# MAX11609EEE-Breakout-Board.net
KiCad netlist of a schematic drawn in EAGLE
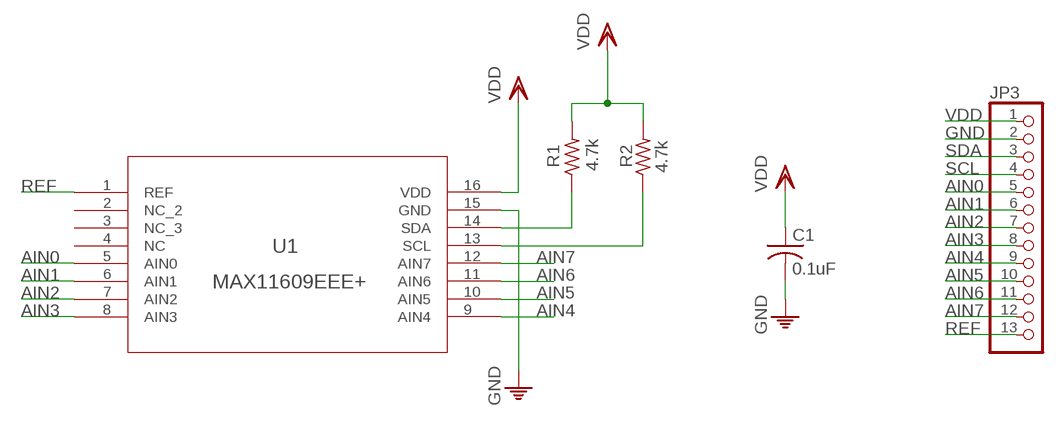
[diagram p0: schematic, sheet 1]

(export (version "E")
  (design (tool "Eeschema 10.0.6"))
  (components
    (comp (ref "C1")
      (value "0.1uF")
      (footprint "eagle-import:C0805")
      (libsource (lib "eagle-import") (part "C-USC0805"))
    )
    (comp (ref "JP3")
      (value "PINHD-1X13")
      (footprint "eagle-import:1X13")
      (libsource (lib "eagle-import") (part "PINHD-1X13"))
    )
    (comp (ref "R1")
      (value "4.7k")
      (footprint "eagle-import:R0805")
      (libsource (lib "eagle-import") (part "R-US_R0805"))
    )
    (comp (ref "R2")
      (value "4.7k")
      (footprint "eagle-import:R0805")
      (libsource (lib "eagle-import") (part "R-US_R0805"))
    )
    (comp (ref "U1")
      (value "MAX11609EEE+")
      (footprint "eagle-import:21-0055H_16")
      (libsource (lib "eagle-import") (part "MAX11609EEE+"))
    )
  )
  (nets
    (net (code "1") (name "/AIN0") (class "Default")
      (node (ref "JP3") (pin "5") (pinfunction "5_5") (pintype "passive"))
      (node (ref "U1") (pin "5") (pinfunction "AIN0_5") (pintype "input"))
    )
    (net (code "2") (name "/AIN1") (class "Default")
      (node (ref "JP3") (pin "6") (pinfunction "6_6") (pintype "passive"))
      (node (ref "U1") (pin "6") (pinfunction "AIN1_6") (pintype "input"))
    )
    (net (code "3") (name "/AIN2") (class "Default")
      (node (ref "JP3") (pin "7") (pinfunction "7_7") (pintype "passive"))
      (node (ref "U1") (pin "7") (pinfunction "AIN2_7") (pintype "input"))
    )
    (net (code "4") (name "/AIN3") (class "Default")
      (node (ref "JP3") (pin "8") (pinfunction "8_8") (pintype "passive"))
      (node (ref "U1") (pin "8") (pinfunction "AIN3_8") (pintype "input"))
    )
    (net (code "5") (name "/AIN4") (class "Default")
      (node (ref "JP3") (pin "9") (pinfunction "9_9") (pintype "passive"))
      (node (ref "U1") (pin "9") (pinfunction "AIN4_9") (pintype "input"))
    )
    (net (code "6") (name "/AIN5") (class "Default")
      (node (ref "JP3") (pin "10") (pinfunction "10_10") (pintype "passive"))
      (node (ref "U1") (pin "10") (pinfunction "AIN5_10") (pintype "input"))
    )
    (net (code "7") (name "/AIN6") (class "Default")
      (node (ref "JP3") (pin "11") (pinfunction "11_11") (pintype "passive"))
      (node (ref "U1") (pin "11") (pinfunction "AIN6_11") (pintype "input"))
    )
    (net (code "8") (name "/AIN7") (class "Default")
      (node (ref "JP3") (pin "12") (pinfunction "12_12") (pintype "passive"))
      (node (ref "U1") (pin "12") (pinfunction "AIN7_12") (pintype "input"))
    )
    (net (code "9") (name "/REF") (class "Default")
      (node (ref "JP3") (pin "13") (pinfunction "13_13") (pintype "passive"))
      (node (ref "U1") (pin "1") (pinfunction "REF_1") (pintype "passive"))
    )
    (net (code "10") (name "/SCL") (class "Default")
      (node (ref "JP3") (pin "4") (pinfunction "4_4") (pintype "passive"))
      (node (ref "R2") (pin "1") (pinfunction "1_1") (pintype "passive"))
      (node (ref "U1") (pin "13") (pinfunction "SCL_13") (pintype "passive"))
    )
    (net (code "11") (name "/SDA") (class "Default")
      (node (ref "JP3") (pin "3") (pinfunction "3_3") (pintype "passive"))
      (node (ref "R1") (pin "1") (pinfunction "1_1") (pintype "passive"))
      (node (ref "U1") (pin "14") (pinfunction "SDA_14") (pintype "passive"))
    )
    (net (code "12") (name "GND") (class "Default")
      (node (ref "C1") (pin "2") (pinfunction "2_2") (pintype "passive"))
      (node (ref "JP3") (pin "2") (pinfunction "2_2") (pintype "passive"))
      (node (ref "U1") (pin "15") (pinfunction "GND_15") (pintype "power_in"))
    )
    (net (code "13") (name "VDD") (class "Default")
      (node (ref "C1") (pin "1") (pinfunction "1_1") (pintype "passive"))
      (node (ref "JP3") (pin "1") (pinfunction "1_1") (pintype "passive"))
      (node (ref "R1") (pin "2") (pinfunction "2_2") (pintype "passive"))
      (node (ref "R2") (pin "2") (pinfunction "2_2") (pintype "passive"))
      (node (ref "U1") (pin "16") (pinfunction "VDD_16") (pintype "power_in"))
    )
    (net (code "14") (name "unconnected-(U1-NC-Pad4)") (class "Default")
      (node (ref "U1") (pin "4") (pinfunction "NC_4") (pintype "passive"))
    )
    (net (code "15") (name "unconnected-(U1-NC_2-Pad2)") (class "Default")
      (node (ref "U1") (pin "2") (pinfunction "NC_2_2") (pintype "passive"))
    )
    (net (code "16") (name "unconnected-(U1-NC_3-Pad3)") (class "Default")
      (node (ref "U1") (pin "3") (pinfunction "NC_3_3") (pintype "passive"))
    )
  )
)
